# gpio4-st.net
KiCad netlist of a schematic drawn in EAGLE
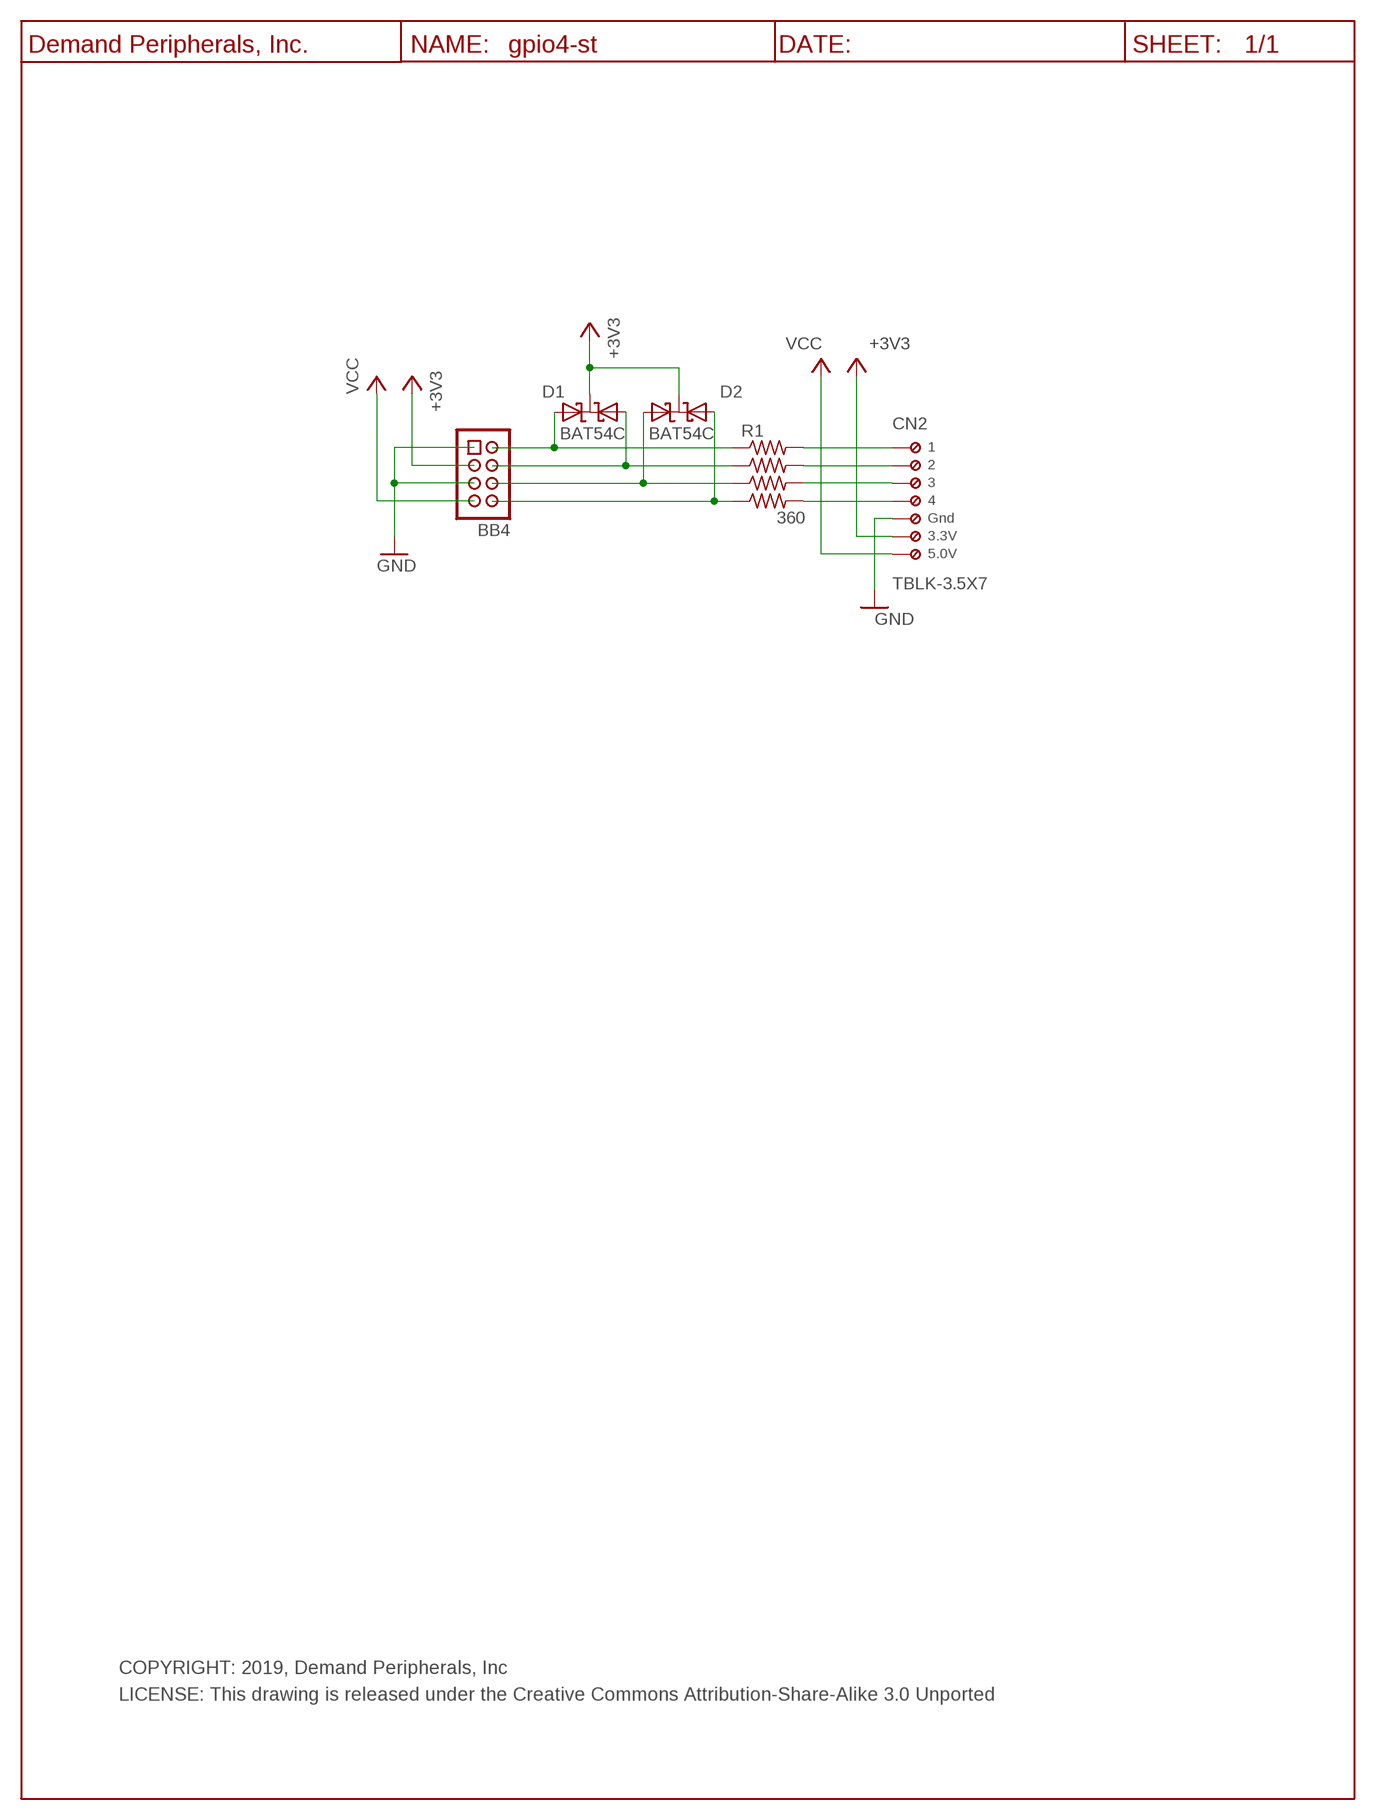
[diagram p0: schematic, sheet 1]

(export (version "E")
  (design (tool "Eeschema 10.0.6"))
  (components
    (comp (ref "BB4")
      (value "BB_CON")
      (footprint "eagle-import:HDR-4X2")
      (libsource (lib "eagle-import") (part "HDR-4X2-SHR"))
    )
    (comp (ref "CN2")
      (value "TBLK-3.5X7")
      (footprint "eagle-import:TBLK-3.5X7")
      (libsource (lib "eagle-import") (part "TBLK-3.5X7"))
    )
    (comp (ref "D1")
      (value "BAT54C")
      (footprint "eagle-import:SOT23")
      (libsource (lib "eagle-import") (part "BAT54C"))
    )
    (comp (ref "D2")
      (value "BAT54C")
      (footprint "eagle-import:SOT23")
      (libsource (lib "eagle-import") (part "BAT54C"))
    )
    (comp (ref "R1")
      (value "360")
      (footprint "eagle-import:R0603")
      (libsource (lib "eagle-import") (part "R360_R0603"))
    )
    (comp (ref "R2")
      (value "360")
      (footprint "eagle-import:R0603")
      (libsource (lib "eagle-import") (part "R360_R0603"))
    )
    (comp (ref "R3")
      (value "360")
      (footprint "eagle-import:R0603")
      (libsource (lib "eagle-import") (part "R360_R0603"))
    )
    (comp (ref "R4")
      (value "360")
      (footprint "eagle-import:R0603")
      (libsource (lib "eagle-import") (part "R360_R0603"))
    )
    (comp (ref "U$1")
      (value "DP_FRAME_P")
      (footprint "eagle-import:P_FRAME")
      (libsource (lib "eagle-import") (part "DP_FRAME_P"))
    )
  )
  (nets
    (net (code "1") (name "+3V3") (class "Default")
      (node (ref "BB4") (pin "3") (pinfunction "3_3") (pintype "passive"))
      (node (ref "CN2") (pin "6") (pinfunction "KL5_6") (pintype "passive"))
      (node (ref "D1") (pin "3") (pinfunction "CC_3") (pintype "passive"))
      (node (ref "D2") (pin "3") (pinfunction "CC_3") (pintype "passive"))
    )
    (net (code "2") (name "GND") (class "Default")
      (node (ref "BB4") (pin "1") (pinfunction "1_1") (pintype "passive"))
      (node (ref "BB4") (pin "5") (pinfunction "5_5") (pintype "passive"))
      (node (ref "CN2") (pin "5") (pinfunction "KL4_5") (pintype "passive"))
    )
    (net (code "3") (name "Net-(CN2-KL)") (class "Default")
      (node (ref "CN2") (pin "1") (pinfunction "KL_1") (pintype "passive"))
      (node (ref "R1") (pin "2") (pinfunction "2_2") (pintype "passive"))
    )
    (net (code "4") (name "Net-(CN2-KL1)") (class "Default")
      (node (ref "CN2") (pin "2") (pinfunction "KL1_2") (pintype "passive"))
      (node (ref "R2") (pin "2") (pinfunction "2_2") (pintype "passive"))
    )
    (net (code "5") (name "Net-(CN2-KL2)") (class "Default")
      (node (ref "CN2") (pin "3") (pinfunction "KL2_3") (pintype "passive"))
      (node (ref "R3") (pin "2") (pinfunction "2_2") (pintype "passive"))
    )
    (net (code "6") (name "Net-(CN2-KL3)") (class "Default")
      (node (ref "CN2") (pin "4") (pinfunction "KL3_4") (pintype "passive"))
      (node (ref "R4") (pin "2") (pinfunction "2_2") (pintype "passive"))
    )
    (net (code "7") (name "Net-(D1-A)") (class "Default")
      (node (ref "BB4") (pin "4") (pinfunction "4_4") (pintype "passive"))
      (node (ref "D1") (pin "2") (pinfunction "A_2") (pintype "passive"))
      (node (ref "R2") (pin "1") (pinfunction "1_1") (pintype "passive"))
    )
    (net (code "8") (name "Net-(D1-A1)") (class "Default")
      (node (ref "BB4") (pin "2") (pinfunction "2_2") (pintype "passive"))
      (node (ref "D1") (pin "1") (pinfunction "A1_1") (pintype "passive"))
      (node (ref "R1") (pin "1") (pinfunction "1_1") (pintype "passive"))
    )
    (net (code "9") (name "Net-(D2-A)") (class "Default")
      (node (ref "BB4") (pin "8") (pinfunction "8_8") (pintype "passive"))
      (node (ref "D2") (pin "2") (pinfunction "A_2") (pintype "passive"))
      (node (ref "R4") (pin "1") (pinfunction "1_1") (pintype "passive"))
    )
    (net (code "10") (name "Net-(D2-A1)") (class "Default")
      (node (ref "BB4") (pin "6") (pinfunction "6_6") (pintype "passive"))
      (node (ref "D2") (pin "1") (pinfunction "A1_1") (pintype "passive"))
      (node (ref "R3") (pin "1") (pinfunction "1_1") (pintype "passive"))
    )
    (net (code "11") (name "VCC") (class "Default")
      (node (ref "BB4") (pin "7") (pinfunction "7_7") (pintype "passive"))
      (node (ref "CN2") (pin "7") (pinfunction "KL6_7") (pintype "passive"))
    )
  )
)
